# PWR_P2V5.net
KiCad netlist of a schematic drawn in Altium Designer
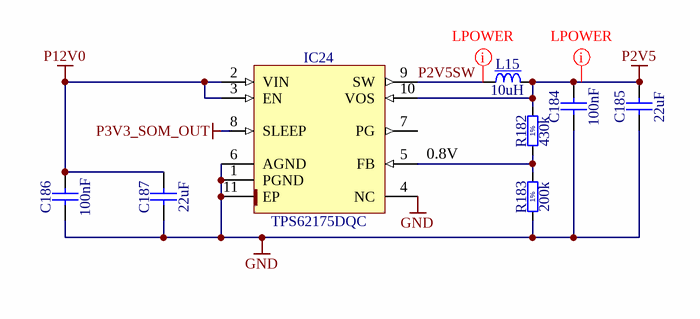
[diagram p0: PWR_P2V5.SchDoc]

(export (version "E")
  (design (tool "Eeschema 10.0.6"))
  (components
    (comp (ref "C184")
      (value "100nF")
      (footprint "CAPC1005X55N")
      (description "Non-polarised capacitor")
      (fields
        (field (name "PART NUMBER") "CC0402_100NF_16V_10%_X5R")
        (field (name "VOLTAGE") "16V")
        (field (name "AUTHOR") "CERN DEM JLC")
      )
      (libsource (lib "Capacitors") (part "Capacitor - non polarized"))
    )
    (comp (ref "C185")
      (value "22uF")
      (footprint "CAPC2012X135N")
      (description "Non-polarised capacitor")
      (fields
        (field (name "PART NUMBER") "CC0805_22UF_16V_10%_X5R")
        (field (name "VOLTAGE") "16V")
        (field (name "AUTHOR") "CERN DEM JLC")
      )
      (libsource (lib "Capacitors") (part "Capacitor - non polarized"))
    )
    (comp (ref "C186")
      (value "100nF")
      (footprint "CAPC1005X55N")
      (description "Non-polarised capacitor")
      (fields
        (field (name "PART NUMBER") "CC0402_100NF_16V_10%_X5R")
        (field (name "VOLTAGE") "16V")
        (field (name "AUTHOR") "CERN DEM JLC")
      )
      (libsource (lib "Capacitors") (part "Capacitor - non polarized"))
    )
    (comp (ref "C187")
      (value "22uF")
      (footprint "CAPC2012X135N")
      (description "Non-polarised capacitor")
      (fields
        (field (name "PART NUMBER") "CC0805_22UF_16V_10%_X5R")
        (field (name "VOLTAGE") "16V")
        (field (name "AUTHOR") "CERN DEM JLC")
      )
      (libsource (lib "Capacitors") (part "Capacitor - non polarized"))
    )
    (comp (ref "IC24")
      (value "TPS62175DQC")
      (footprint "SON50P200X300X80-11N-R94X250")
      (description "4.75-28VDC to 1-6VDC, 500mA Step-Down Converter With Sleep Mode")
      (fields (field (name "MANUFACTURER") "TEXAS INSTRUMENTS") (field (name "AUTHOR") "CERN DEM JMW"))
      (libsource (lib "ICs And Semiconductors") (part "TPS62175"))
    )
    (comp (ref "L15")
      (value "10uH")
      (footprint "IND_MURATA-PS_8400")
      (description "Inductor With Core")
      (fields
        (field (name "PART NUMBER") "IND_10UH_10%_MURATA-PS_8400")
        (field (name "POWER") "950mA")
        (field (name "AUTHOR") "CERN DEM JLC")
      )
      (libsource (lib "Inductors & Transformers") (part "Inductor With Magnetic core"))
    )
    (comp (ref "R182")
      (value "430k")
      (footprint "RESC1005X40N")
      (description "Resistor - 1%")
      (fields
        (field (name "PART NUMBER") "R0402_430K_1%_0.0625W_100PPM")
        (field (name "POWER") "0.0625W")
        (field (name "AUTHOR") "CERN DEM JLC")
      )
      (libsource (lib "Resistors") (part "Resistor - 1%"))
    )
    (comp (ref "R183")
      (value "200k")
      (footprint "RESC1005X40N")
      (description "Resistor - 1%")
      (fields
        (field (name "PART NUMBER") "R0402_200K_1%_0.0625W_100PPM")
        (field (name "POWER") "0.0625W")
        (field (name "AUTHOR") "CERN DEM JLC")
      )
      (libsource (lib "Resistors") (part "Resistor - 1%"))
    )
  )
  (nets
    (net (code "1") (name "/P2V5SW") (class "Default")
      (node (ref "IC24") (pin "9") (pinfunction "SW_9") (pintype "output"))
      (node (ref "L15") (pin "1") (pinfunction "1_1") (pintype "passive"))
    )
    (net (code "2") (name "GND") (class "Default")
      (node (ref "C184") (pin "1") (pinfunction "1_1") (pintype "passive"))
      (node (ref "C185") (pin "1") (pinfunction "1_1") (pintype "passive"))
      (node (ref "C186") (pin "1") (pinfunction "1_1") (pintype "passive"))
      (node (ref "C187") (pin "1") (pinfunction "1_1") (pintype "passive"))
      (node (ref "IC24") (pin "1") (pinfunction "PGND_1") (pintype "power_in"))
      (node (ref "IC24") (pin "11") (pinfunction "EP_11") (pintype "power_in"))
      (node (ref "IC24") (pin "4") (pinfunction "NC_4") (pintype "passive"))
      (node (ref "IC24") (pin "6") (pinfunction "AGND_6") (pintype "power_in"))
      (node (ref "R183") (pin "1") (pinfunction "1_1") (pintype "passive"))
    )
    (net (code "3") (name "Net-(IC24-FB)") (class "Default")
      (node (ref "IC24") (pin "5") (pinfunction "FB_5") (pintype "input"))
      (node (ref "R182") (pin "1") (pinfunction "1_1") (pintype "passive"))
      (node (ref "R183") (pin "2") (pinfunction "2_2") (pintype "passive"))
    )
    (net (code "4") (name "P2V5") (class "Default")
      (node (ref "C184") (pin "2") (pinfunction "2_2") (pintype "passive"))
      (node (ref "C185") (pin "2") (pinfunction "2_2") (pintype "passive"))
      (node (ref "IC24") (pin "10") (pinfunction "VOS_10") (pintype "input"))
      (node (ref "L15") (pin "2") (pinfunction "2_2") (pintype "passive"))
      (node (ref "R182") (pin "2") (pinfunction "2_2") (pintype "passive"))
    )
    (net (code "5") (name "P3V3_SOM_OUT") (class "Default")
      (node (ref "IC24") (pin "8") (pinfunction "SLEEP_8") (pintype "input"))
    )
    (net (code "6") (name "P12V0") (class "Default")
      (node (ref "C186") (pin "2") (pinfunction "2_2") (pintype "passive"))
      (node (ref "C187") (pin "2") (pinfunction "2_2") (pintype "passive"))
      (node (ref "IC24") (pin "2") (pinfunction "VIN_2") (pintype "input"))
      (node (ref "IC24") (pin "3") (pinfunction "EN_3") (pintype "input"))
    )
    (net (code "7") (name "unconnected-(IC24-PG-Pad7)") (class "Default")
      (node (ref "IC24") (pin "7") (pinfunction "PG_7") (pintype "output"))
    )
  )
)
